# MCU.net
KiCad netlist of a schematic drawn in Altium Designer
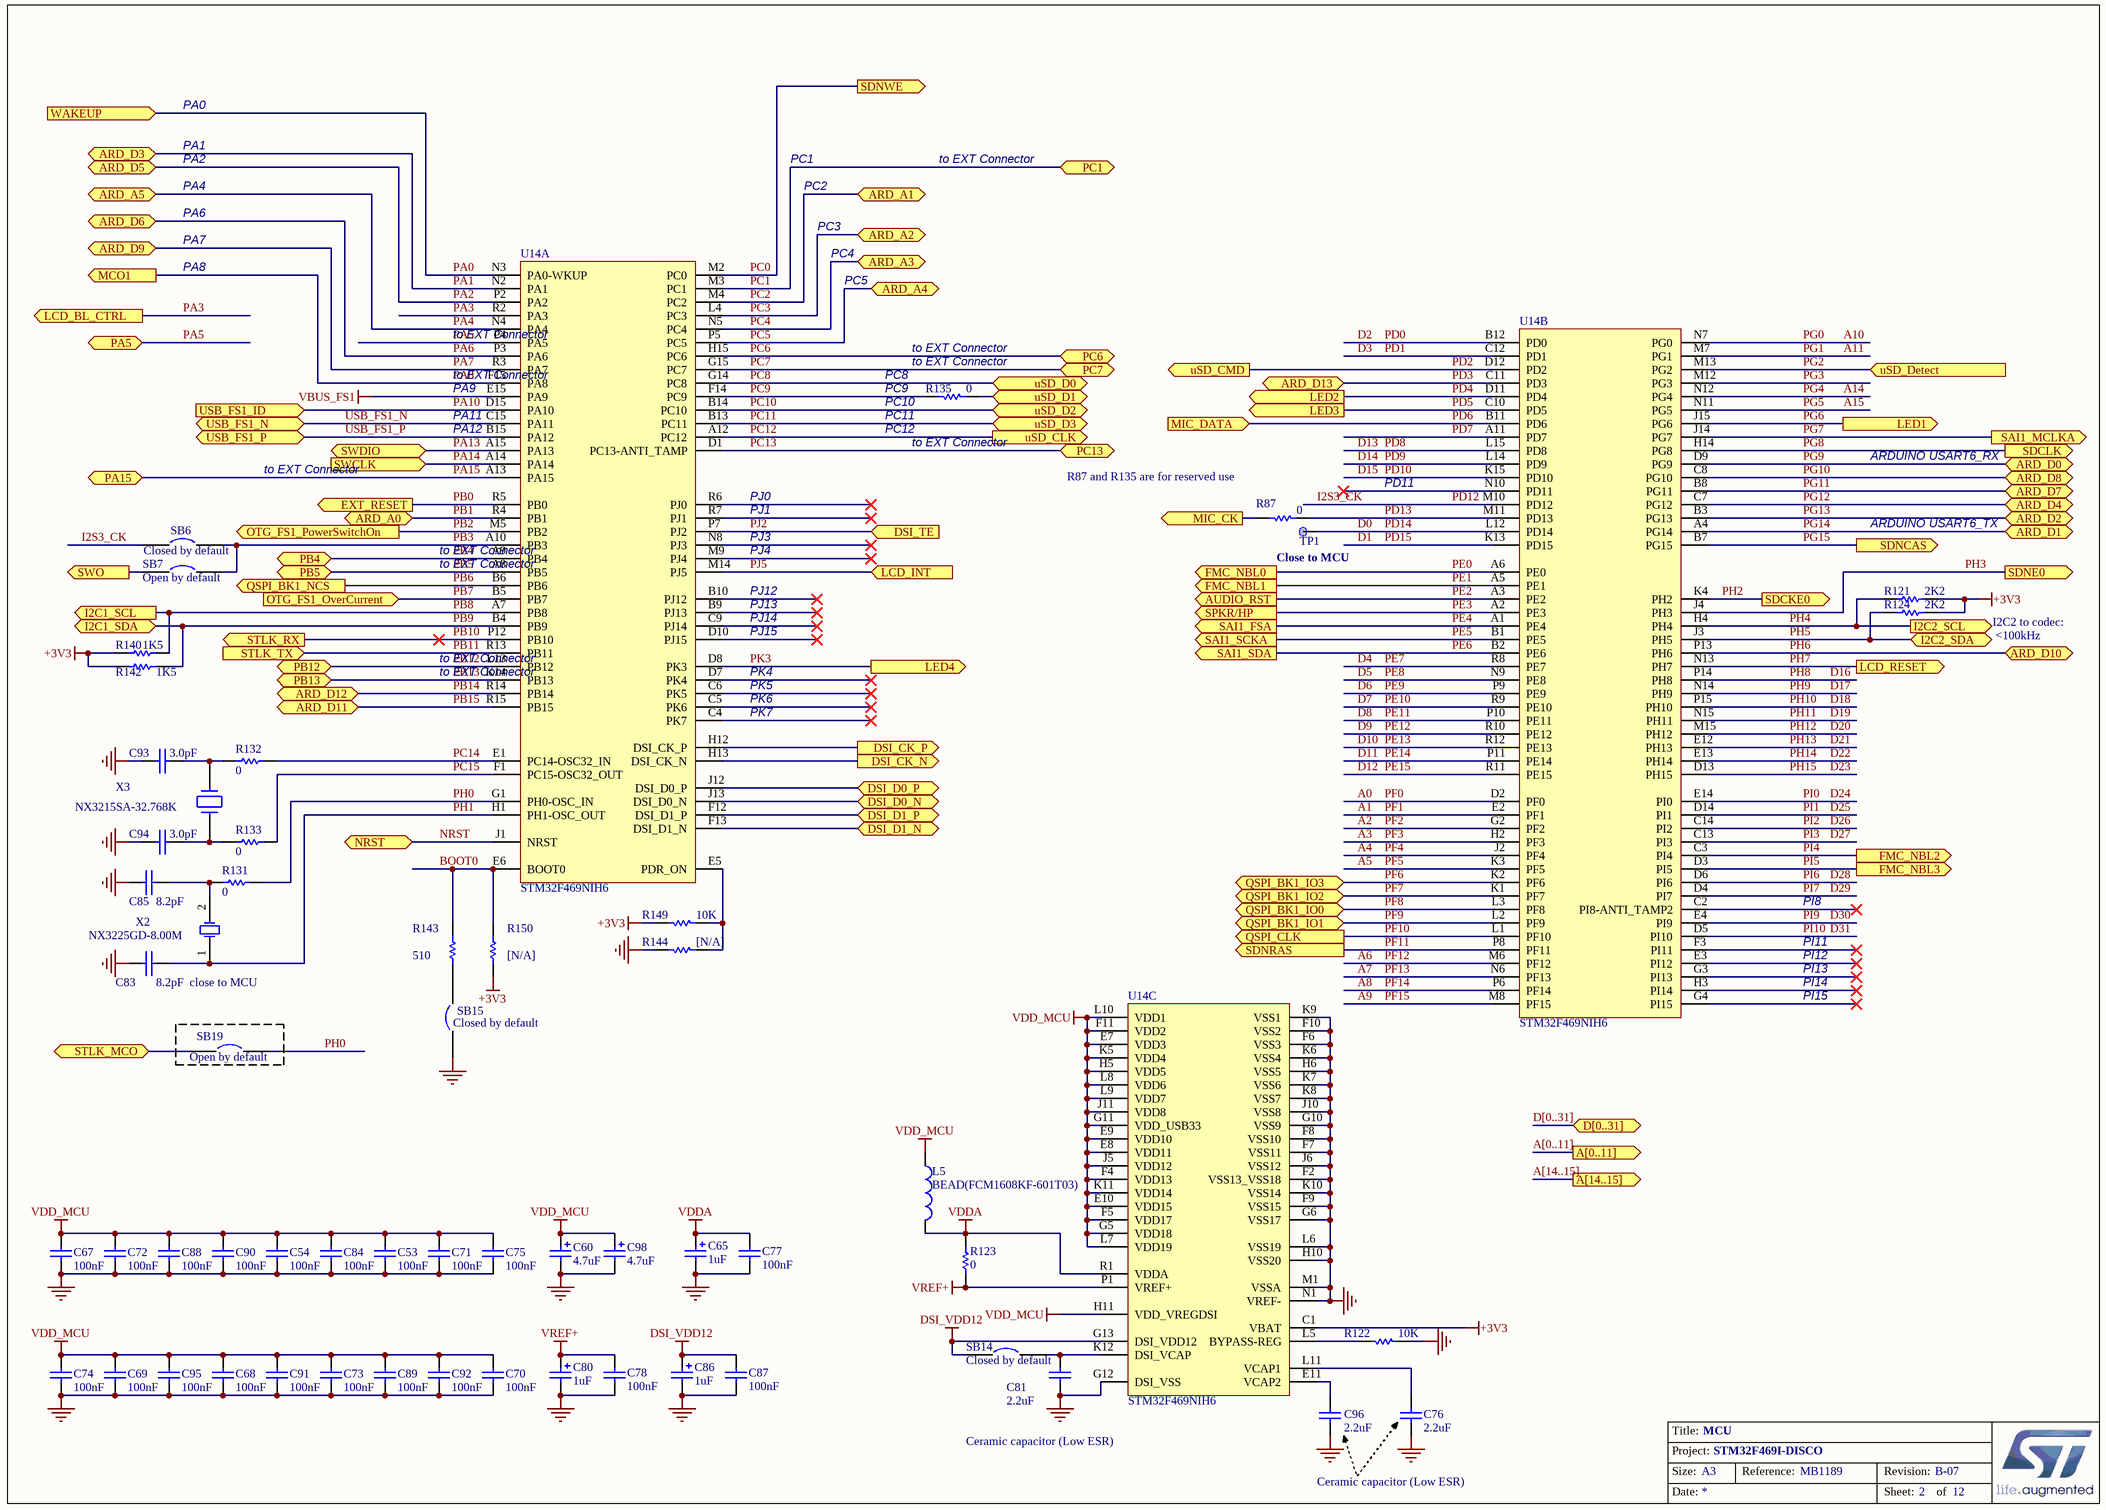
[diagram p0: MCU.SchDoc]

(export (version "E")
  (design (tool "Eeschema 10.0.6"))
  (components
    (comp (ref "C53")
      (value "100nF")
      (footprint "0402C")
      (description "Capacitor")
      (fields (field (name "PUBLISHER") "Altium Limited"))
      (libsource (lib "Miscellaneous Devices") (part "CAP"))
    )
    (comp (ref "C54")
      (value "100nF")
      (footprint "0402C")
      (description "Capacitor")
      (fields (field (name "PUBLISHER") "Altium Limited"))
      (libsource (lib "Miscellaneous Devices") (part "CAP"))
    )
    (comp (ref "C60")
      (value "4.7uF")
      (footprint "TAN-A")
      (description "Polarized Capacitor (Radial)")
      (fields (field (name "PUBLISHER") "Altium Limited"))
      (libsource (lib "Miscellaneous Devices") (part "Cap Pol1"))
    )
    (comp (ref "C65")
      (value "1uF")
      (footprint "TAN-A")
      (description "Polarized Capacitor (Radial)")
      (fields (field (name "PUBLISHER") "Altium Limited"))
      (libsource (lib "Miscellaneous Devices") (part "Cap Pol1"))
    )
    (comp (ref "C67")
      (value "100nF")
      (footprint "0402C")
      (description "Capacitor")
      (fields (field (name "PUBLISHER") "Altium Limited"))
      (libsource (lib "Miscellaneous Devices") (part "CAP"))
    )
    (comp (ref "C68")
      (value "100nF")
      (footprint "0402C")
      (description "Capacitor")
      (fields (field (name "PUBLISHER") "Altium Limited"))
      (libsource (lib "Miscellaneous Devices") (part "CAP"))
    )
    (comp (ref "C69")
      (value "100nF")
      (footprint "0402C")
      (description "Capacitor")
      (fields (field (name "PUBLISHER") "Altium Limited"))
      (libsource (lib "Miscellaneous Devices") (part "CAP"))
    )
    (comp (ref "C70")
      (value "100nF")
      (footprint "0402C")
      (description "Capacitor")
      (fields (field (name "PUBLISHER") "Altium Limited"))
      (libsource (lib "Miscellaneous Devices") (part "CAP"))
    )
    (comp (ref "C71")
      (value "100nF")
      (footprint "0402C")
      (description "Capacitor")
      (fields (field (name "PUBLISHER") "Altium Limited"))
      (libsource (lib "Miscellaneous Devices") (part "CAP"))
    )
    (comp (ref "C72")
      (value "100nF")
      (footprint "0402C")
      (description "Capacitor")
      (fields (field (name "PUBLISHER") "Altium Limited"))
      (libsource (lib "Miscellaneous Devices") (part "CAP"))
    )
    (comp (ref "C73")
      (value "100nF")
      (footprint "0402C")
      (description "Capacitor")
      (fields (field (name "PUBLISHER") "Altium Limited"))
      (libsource (lib "Miscellaneous Devices") (part "CAP"))
    )
    (comp (ref "C74")
      (value "100nF")
      (footprint "0402C")
      (description "Capacitor")
      (fields (field (name "PUBLISHER") "Altium Limited"))
      (libsource (lib "Miscellaneous Devices") (part "CAP"))
    )
    (comp (ref "C75")
      (value "100nF")
      (footprint "0402C")
      (description "Capacitor")
      (fields (field (name "PUBLISHER") "Altium Limited"))
      (libsource (lib "Miscellaneous Devices") (part "CAP"))
    )
    (comp (ref "C76")
      (value "2.2uF")
      (footprint "1206C")
      (description "Capacitor")
      (fields (field (name "PUBLISHER") "Altium Limited"))
      (libsource (lib "Miscellaneous Devices") (part "Cap"))
    )
    (comp (ref "C77")
      (value "100nF")
      (footprint "0402C")
      (description "Capacitor")
      (fields (field (name "PUBLISHER") "Altium Limited"))
      (libsource (lib "Miscellaneous Devices") (part "Cap"))
    )
    (comp (ref "C78")
      (value "100nF")
      (footprint "0402C")
      (description "Capacitor")
      (fields (field (name "PUBLISHER") "Altium Limited"))
      (libsource (lib "Miscellaneous Devices") (part "Cap"))
    )
    (comp (ref "C80")
      (value "1uF")
      (footprint "TAN-A")
      (description "Polarized Capacitor (Radial)")
      (fields (field (name "PUBLISHER") "Altium Limited"))
      (libsource (lib "Miscellaneous Devices") (part "Cap Pol1"))
    )
    (comp (ref "C81")
      (value "2.2uF")
      (footprint "1206C")
      (description "Capacitor")
      (fields (field (name "PUBLISHER") "Altium Limited"))
      (libsource (lib "Miscellaneous Devices") (part "Cap"))
    )
    (comp (ref "C83")
      (value "8.2pF")
      (footprint "0603C")
      (description "Capacitor")
      (libsource (lib "*") (part "CAP"))
    )
    (comp (ref "C84")
      (value "100nF")
      (footprint "0402C")
      (description "Capacitor")
      (fields (field (name "PUBLISHER") "Altium Limited"))
      (libsource (lib "Miscellaneous Devices") (part "CAP"))
    )
    (comp (ref "C85")
      (value "8.2pF")
      (footprint "0603C")
      (description "Capacitor")
      (libsource (lib "*") (part "CAP"))
    )
    (comp (ref "C86")
      (value "1uF")
      (footprint "TAN-A")
      (description "Polarized Capacitor (Radial)")
      (fields (field (name "PUBLISHER") "Altium Limited"))
      (libsource (lib "Miscellaneous Devices") (part "Cap Pol1"))
    )
    (comp (ref "C87")
      (value "100nF")
      (footprint "0402C")
      (description "Capacitor")
      (fields (field (name "PUBLISHER") "Altium Limited"))
      (libsource (lib "Miscellaneous Devices") (part "Cap"))
    )
    (comp (ref "C88")
      (value "100nF")
      (footprint "0402C")
      (description "Capacitor")
      (fields (field (name "PUBLISHER") "Altium Limited"))
      (libsource (lib "Miscellaneous Devices") (part "CAP"))
    )
    (comp (ref "C89")
      (value "100nF")
      (footprint "0402C")
      (description "Capacitor")
      (fields (field (name "PUBLISHER") "Altium Limited"))
      (libsource (lib "Miscellaneous Devices") (part "CAP"))
    )
    (comp (ref "C90")
      (value "100nF")
      (footprint "0402C")
      (description "Capacitor")
      (fields (field (name "PUBLISHER") "Altium Limited"))
      (libsource (lib "Miscellaneous Devices") (part "CAP"))
    )
    (comp (ref "C91")
      (value "100nF")
      (footprint "0402C")
      (description "Capacitor")
      (fields (field (name "PUBLISHER") "Altium Limited"))
      (libsource (lib "Miscellaneous Devices") (part "CAP"))
    )
    (comp (ref "C92")
      (value "100nF")
      (footprint "0402C")
      (description "Capacitor")
      (fields (field (name "PUBLISHER") "Altium Limited"))
      (libsource (lib "Miscellaneous Devices") (part "CAP"))
    )
    (comp (ref "C93")
      (value "3.0pF")
      (footprint "0603C")
      (description "Capacitor")
      (libsource (lib "") (part "CAP_1"))
    )
    (comp (ref "C94")
      (value "3.0pF")
      (footprint "0603C")
      (description "Capacitor")
      (libsource (lib "") (part "CAP_1"))
    )
    (comp (ref "C95")
      (value "100nF")
      (footprint "0402C")
      (description "Capacitor")
      (fields (field (name "PUBLISHER") "Altium Limited"))
      (libsource (lib "Miscellaneous Devices") (part "CAP"))
    )
    (comp (ref "C96")
      (value "2.2uF")
      (footprint "1206C")
      (description "Capacitor")
      (fields (field (name "PUBLISHER") "Altium Limited"))
      (libsource (lib "Miscellaneous Devices") (part "Cap"))
    )
    (comp (ref "C98")
      (value "4.7uF")
      (footprint "TAN-A")
      (description "Polarized Capacitor (Radial)")
      (fields (field (name "PUBLISHER") "Altium Limited"))
      (libsource (lib "Miscellaneous Devices") (part "Cap Pol1"))
    )
    (comp (ref "L5")
      (value "BEAD(FCM1608KF-601T03)")
      (footprint "0603L")
      (description "Inductor")
      (fields (field (name "PUBLISHER") "Altium Limited"))
      (libsource (lib "Miscellaneous Devices") (part "Inductor"))
    )
    (comp (ref "R87")
      (value "0")
      (footprint "0603R")
      (description "Resistor")
      (fields (field (name "PUBLISHER") "Altium Limited"))
      (libsource (lib "Miscellaneous Devices") (part "Res1"))
    )
    (comp (ref "R121")
      (value "2K2")
      (footprint "0603R")
      (description "Resistor")
      (fields (field (name "PUBLISHER") "Altium Limited"))
      (libsource (lib "") (part "Res1_1"))
    )
    (comp (ref "R122")
      (value "10K")
      (footprint "0402R")
      (description "Resistor")
      (fields (field (name "PUBLISHER") "Altium Limited"))
      (libsource (lib "") (part "Res1_1"))
    )
    (comp (ref "R123")
      (value "0")
      (footprint "0603R")
      (description "Resistor")
      (fields (field (name "PUBLISHER") "Altium Limited"))
      (libsource (lib "Miscellaneous Devices") (part "Res1"))
    )
    (comp (ref "R124")
      (value "2K2")
      (footprint "0603R")
      (description "Resistor")
      (fields (field (name "PUBLISHER") "Altium Limited"))
      (libsource (lib "") (part "Res1_1"))
    )
    (comp (ref "R131")
      (value "0")
      (footprint "0603R")
      (description "Resistor")
      (fields (field (name "PUBLISHER") "Altium Limited"))
      (libsource (lib "Miscellaneous Devices") (part "Res1"))
    )
    (comp (ref "R132")
      (value "0")
      (footprint "0603R")
      (description "Resistor")
      (fields (field (name "PUBLISHER") "Altium Limited"))
      (libsource (lib "") (part "Res1_1"))
    )
    (comp (ref "R133")
      (value "0")
      (footprint "0603R")
      (description "Resistor")
      (fields (field (name "PUBLISHER") "Altium Limited"))
      (libsource (lib "") (part "Res1_1"))
    )
    (comp (ref "R135")
      (value "0")
      (footprint "0603R")
      (description "Resistor")
      (fields (field (name "PUBLISHER") "Altium Limited"))
      (libsource (lib "Miscellaneous Devices") (part "Res1"))
    )
    (comp (ref "R140")
      (value "1K5")
      (footprint "0603R")
      (description "Resistor")
      (fields (field (name "PUBLISHER") "Altium Limited"))
      (libsource (lib "") (part "Res1_1"))
    )
    (comp (ref "R142")
      (value "1K5")
      (footprint "0603R")
      (description "Resistor")
      (fields (field (name "PUBLISHER") "Altium Limited"))
      (libsource (lib "") (part "Res1_1"))
    )
    (comp (ref "R143")
      (value "510")
      (footprint "0603R")
      (description "Resistor")
      (fields (field (name "PUBLISHER") "Altium Limited"))
      (libsource (lib "Miscellaneous Devices") (part "res1"))
    )
    (comp (ref "R144")
      (value "[N/A]")
      (footprint "0603R")
      (description "Resistor")
      (fields (field (name "PUBLISHER") "Altium Limited"))
      (libsource (lib "Miscellaneous Devices") (part "Res1"))
    )
    (comp (ref "R149")
      (value "10K")
      (footprint "0402R")
      (description "Resistor")
      (fields (field (name "PUBLISHER") "Altium Limited"))
      (libsource (lib "Miscellaneous Devices") (part "Res1"))
    )
    (comp (ref "R150")
      (value "[N/A]")
      (footprint "0603R")
      (description "Resistor")
      (fields (field (name "PUBLISHER") "Altium Limited"))
      (libsource (lib "Miscellaneous Devices") (part "res1"))
    )
    (comp (ref "SB6")
      (value "Closed by default")
      (footprint "SB_0603")
      (description "Circuit Breaker")
      (fields (field (name "PUBLISHER") "Altium Limited"))
      (libsource (lib "Miscellaneous Devices") (part "Circuit Breaker"))
    )
    (comp (ref "SB7")
      (value "Open by default")
      (footprint "SB_0603")
      (description "Circuit Breaker")
      (fields (field (name "PUBLISHER") "Altium Limited"))
      (libsource (lib "Miscellaneous Devices") (part "Circuit Breaker"))
    )
    (comp (ref "SB14")
      (value "Closed by default")
      (footprint "SB_0603")
      (description "Circuit Breaker")
      (fields (field (name "PUBLISHER") "Altium Limited"))
      (libsource (lib "Miscellaneous Devices") (part "Circuit Breaker"))
    )
    (comp (ref "SB15")
      (value "Closed by default")
      (footprint "SB_0603")
      (description "Circuit Breaker")
      (fields (field (name "PUBLISHER") "Altium Limited"))
      (libsource (lib "Miscellaneous Devices") (part "Circuit Breaker"))
    )
    (comp (ref "SB19")
      (value "Open by default")
      (footprint "SB_0603")
      (description "Circuit Breaker")
      (fields (field (name "PUBLISHER") "Altium Limited"))
      (libsource (lib "Miscellaneous Devices") (part "Circuit Breaker"))
    )
    (comp (ref "TP1") (value "TP") (footprint "TP_C40") (libsource (lib "Almos") (part "TP")))
    (comp (ref "U14")
      (value "STM32F469NIH6")
      (footprint "BGA216_0R8_13X13")
      (libsource (lib "MB1165") (part "Manta_Dragon_TFBGA216"))
    )
    (comp (ref "X2")
      (value "NX3225GD-8.00M")
      (footprint "XTAL_2SM_3R2X2R5_H1")
      (description "Crystal 8Mhz, 8pF, -+50PPM, SMD")
      (libsource (lib "MCD_TOOLS") (part "XTAL_8M_NX3225GD"))
    )
    (comp (ref "X3")
      (value "NX3215SA-32.768K")
      (footprint "XTAL_2SM_3R2X1R5")
      (description "Crystal 32.768kHz, 6pF, -+20PPM, NDK only for ST, Type NX3215SA,  NDK Spec EXS00A-MU00525")
      (libsource (lib "MCD_TOOLS") (part "XTAL_32K_NX3215SA"))
    )
  )
  (nets
    (net (code "1") (name "+3V3") (class "Default")
      (node (ref "R121") (pin "1") (pinfunction "1_1") (pintype "passive"))
      (node (ref "R124") (pin "1") (pinfunction "1_1") (pintype "passive"))
      (node (ref "R140") (pin "1") (pinfunction "1_1") (pintype "passive"))
      (node (ref "R142") (pin "1") (pinfunction "1_1") (pintype "passive"))
      (node (ref "R149") (pin "2") (pinfunction "2_2") (pintype "passive"))
      (node (ref "R150") (pin "2") (pinfunction "2_2") (pintype "passive"))
      (node (ref "U14") (pin "C1") (pinfunction "VBAT_C1") (pintype "passive"))
    )
    (net (code "2") (name "/A0") (class "Default")
      (node (ref "U14") (pin "D2") (pinfunction "PF0_D2") (pintype "passive"))
    )
    (net (code "3") (name "/A1") (class "Default")
      (node (ref "U14") (pin "E2") (pinfunction "PF1_E2") (pintype "passive"))
    )
    (net (code "4") (name "/A2") (class "Default")
      (node (ref "U14") (pin "G2") (pinfunction "PF2_G2") (pintype "passive"))
    )
    (net (code "5") (name "/A3") (class "Default")
      (node (ref "U14") (pin "H2") (pinfunction "PF3_H2") (pintype "passive"))
    )
    (net (code "6") (name "/A4") (class "Default")
      (node (ref "U14") (pin "J2") (pinfunction "PF4_J2") (pintype "passive"))
    )
    (net (code "7") (name "/A5") (class "Default")
      (node (ref "U14") (pin "K3") (pinfunction "PF5_K3") (pintype "passive"))
    )
    (net (code "8") (name "/A6") (class "Default")
      (node (ref "U14") (pin "M6") (pinfunction "PF12_M6") (pintype "passive"))
    )
    (net (code "9") (name "/A7") (class "Default")
      (node (ref "U14") (pin "N6") (pinfunction "PF13_N6") (pintype "passive"))
    )
    (net (code "10") (name "/A8") (class "Default")
      (node (ref "U14") (pin "P6") (pinfunction "PF14_P6") (pintype "passive"))
    )
    (net (code "11") (name "/A9") (class "Default")
      (node (ref "U14") (pin "M8") (pinfunction "PF15_M8") (pintype "passive"))
    )
    (net (code "12") (name "/A10") (class "Default")
      (node (ref "U14") (pin "N7") (pinfunction "PG0_N7") (pintype "passive"))
    )
    (net (code "13") (name "/A11") (class "Default")
      (node (ref "U14") (pin "M7") (pinfunction "PG1_M7") (pintype "passive"))
    )
    (net (code "14") (name "/A14") (class "Default")
      (node (ref "U14") (pin "N12") (pinfunction "PG4_N12") (pintype "passive"))
    )
    (net (code "15") (name "/A15") (class "Default")
      (node (ref "U14") (pin "N11") (pinfunction "PG5_N11") (pintype "passive"))
    )
    (net (code "18") (name "/BOOT0") (class "Default")
      (node (ref "R143") (pin "1") (pinfunction "1_1") (pintype "passive"))
      (node (ref "R150") (pin "1") (pinfunction "1_1") (pintype "passive"))
      (node (ref "U14") (pin "E6") (pinfunction "BOOT0_E6") (pintype "passive"))
    )
    (net (code "19") (name "/D0") (class "Default")
      (node (ref "TP1") (pin "1") (pinfunction "1_1") (pintype "passive"))
      (node (ref "U14") (pin "L12") (pinfunction "PD14_L12") (pintype "passive"))
    )
    (net (code "20") (name "/D1") (class "Default")
      (node (ref "U14") (pin "K13") (pinfunction "PD15_K13") (pintype "passive"))
    )
    (net (code "21") (name "/D2") (class "Default")
      (node (ref "U14") (pin "B12") (pinfunction "PD0_B12") (pintype "passive"))
    )
    (net (code "22") (name "/D3") (class "Default")
      (node (ref "U14") (pin "C12") (pinfunction "PD1_C12") (pintype "passive"))
    )
    (net (code "23") (name "/D4") (class "Default")
      (node (ref "U14") (pin "R8") (pinfunction "PE7_R8") (pintype "passive"))
    )
    (net (code "24") (name "/D5") (class "Default")
      (node (ref "U14") (pin "N9") (pinfunction "PE8_N9") (pintype "passive"))
    )
    (net (code "25") (name "/D6") (class "Default")
      (node (ref "U14") (pin "P9") (pinfunction "PE9_P9") (pintype "passive"))
    )
    (net (code "26") (name "/D7") (class "Default")
      (node (ref "U14") (pin "R9") (pinfunction "PE10_R9") (pintype "passive"))
    )
    (net (code "27") (name "/D8") (class "Default")
      (node (ref "U14") (pin "P10") (pinfunction "PE11_P10") (pintype "passive"))
    )
    (net (code "28") (name "/D9") (class "Default")
      (node (ref "U14") (pin "R10") (pinfunction "PE12_R10") (pintype "passive"))
    )
    (net (code "29") (name "/D10") (class "Default")
      (node (ref "U14") (pin "R12") (pinfunction "PE13_R12") (pintype "passive"))
    )
    (net (code "30") (name "/D11") (class "Default")
      (node (ref "U14") (pin "P11") (pinfunction "PE14_P11") (pintype "passive"))
    )
    (net (code "31") (name "/D12") (class "Default")
      (node (ref "U14") (pin "R11") (pinfunction "PE15_R11") (pintype "passive"))
    )
    (net (code "32") (name "/D13") (class "Default")
      (node (ref "U14") (pin "L15") (pinfunction "PD8_L15") (pintype "passive"))
    )
    (net (code "33") (name "/D14") (class "Default")
      (node (ref "U14") (pin "L14") (pinfunction "PD9_L14") (pintype "passive"))
    )
    (net (code "34") (name "/D15") (class "Default")
      (node (ref "U14") (pin "K15") (pinfunction "PD10_K15") (pintype "passive"))
    )
    (net (code "35") (name "/D16") (class "Default")
      (node (ref "U14") (pin "P14") (pinfunction "PH8_P14") (pintype "passive"))
    )
    (net (code "36") (name "/D17") (class "Default")
      (node (ref "U14") (pin "N14") (pinfunction "PH9_N14") (pintype "passive"))
    )
    (net (code "37") (name "/D18") (class "Default")
      (node (ref "U14") (pin "P15") (pinfunction "PH10_P15") (pintype "passive"))
    )
    (net (code "38") (name "/D19") (class "Default")
      (node (ref "U14") (pin "N15") (pinfunction "PH11_N15") (pintype "passive"))
    )
    (net (code "39") (name "/D20") (class "Default")
      (node (ref "U14") (pin "M15") (pinfunction "PH12_M15") (pintype "passive"))
    )
    (net (code "40") (name "/D21") (class "Default")
      (node (ref "U14") (pin "E12") (pinfunction "PH13_E12") (pintype "passive"))
    )
    (net (code "41") (name "/D22") (class "Default")
      (node (ref "U14") (pin "E13") (pinfunction "PH14_E13") (pintype "passive"))
    )
    (net (code "42") (name "/D23") (class "Default")
      (node (ref "U14") (pin "D13") (pinfunction "PH15_D13") (pintype "passive"))
    )
    (net (code "43") (name "/D24") (class "Default")
      (node (ref "U14") (pin "E14") (pinfunction "PI0_E14") (pintype "passive"))
    )
    (net (code "44") (name "/D25") (class "Default")
      (node (ref "U14") (pin "D14") (pinfunction "PI1_D14") (pintype "passive"))
    )
    (net (code "45") (name "/D26") (class "Default")
      (node (ref "U14") (pin "C14") (pinfunction "PI2_C14") (pintype "passive"))
    )
    (net (code "46") (name "/D27") (class "Default")
      (node (ref "U14") (pin "C13") (pinfunction "PI3_C13") (pintype "passive"))
    )
    (net (code "47") (name "/D28") (class "Default")
      (node (ref "U14") (pin "D6") (pinfunction "PI6_D6") (pintype "passive"))
    )
    (net (code "48") (name "/D29") (class "Default")
      (node (ref "U14") (pin "D4") (pinfunction "PI7_D4") (pintype "passive"))
    )
    (net (code "49") (name "/D30") (class "Default")
      (node (ref "U14") (pin "E4") (pinfunction "PI9_E4") (pintype "passive"))
    )
    (net (code "50") (name "/D31") (class "Default")
      (node (ref "U14") (pin "D5") (pinfunction "PI10_D5") (pintype "passive"))
    )
    (net (code "51") (name "/DSI_CK_N") (class "Default")
      (node (ref "U14") (pin "H13") (pinfunction "DSI_CK_N_H13") (pintype "passive"))
    )
    (net (code "52") (name "/DSI_CK_P") (class "Default")
      (node (ref "U14") (pin "H12") (pinfunction "DSI_CK_P_H12") (pintype "passive"))
    )
    (net (code "53") (name "/DSI_D0_N") (class "Default")
      (node (ref "U14") (pin "J13") (pinfunction "DSI_D0_N_J13") (pintype "passive"))
    )
    (net (code "54") (name "/DSI_D0_P") (class "Default")
      (node (ref "U14") (pin "J12") (pinfunction "DSI_D0_P_J12") (pintype "passive"))
    )
    (net (code "55") (name "/DSI_D1_N") (class "Default")
      (node (ref "U14") (pin "F13") (pinfunction "DSI_D1_N_F13") (pintype "passive"))
    )
    (net (code "56") (name "/DSI_D1_P") (class "Default")
      (node (ref "U14") (pin "F12") (pinfunction "DSI_D1_P_F12") (pintype "passive"))
    )
    (net (code "58") (name "/I2S3_CK") (class "Default")
      (node (ref "SB6") (pin "1") (pinfunction "1_1") (pintype "passive"))
      (node (ref "U14") (pin "M10") (pinfunction "PD12_M10") (pintype "passive"))
    )
    (net (code "59") (name "/MIC_CK") (class "Default")
      (node (ref "R87") (pin "1") (pinfunction "1_1") (pintype "passive"))
    )
    (net (code "60") (name "/NRST") (class "Default")
      (node (ref "U14") (pin "J1") (pinfunction "NRST_J1") (pintype "passive"))
    )
    (net (code "61") (name "/PA0") (class "Default")
      (node (ref "U14") (pin "N3") (pinfunction "PA0-WKUP_N3") (pintype "passive"))
    )
    (net (code "62") (name "/PA1") (class "Default")
      (node (ref "U14") (pin "N2") (pinfunction "PA1_N2") (pintype "passive"))
    )
    (net (code "63") (name "/PA2") (class "Default")
      (node (ref "U14") (pin "P2") (pinfunction "PA2_P2") (pintype "passive"))
    )
    (net (code "64") (name "/PA3") (class "Default")
      (node (ref "U14") (pin "R2") (pinfunction "PA3_R2") (pintype "passive"))
    )
    (net (code "65") (name "/PA4") (class "Default")
      (node (ref "U14") (pin "N4") (pinfunction "PA4_N4") (pintype "passive"))
    )
    (net (code "66") (name "/PA5") (class "Default")
      (node (ref "U14") (pin "P4") (pinfunction "PA5_P4") (pintype "passive"))
    )
    (net (code "67") (name "/PA6") (class "Default")
      (node (ref "U14") (pin "P3") (pinfunction "PA6_P3") (pintype "passive"))
    )
    (net (code "68") (name "/PA7") (class "Default")
      (node (ref "U14") (pin "R3") (pinfunction "PA7_R3") (pintype "passive"))
    )
    (net (code "69") (name "/PA8") (class "Default")
      (node (ref "U14") (pin "F15") (pinfunction "PA8_F15") (pintype "passive"))
    )
    (net (code "70") (name "/PA10") (class "Default")
      (node (ref "U14") (pin "D15") (pinfunction "PA10_D15") (pintype "passive"))
    )
    (net (code "71") (name "/PA13") (class "Default")
      (node (ref "U14") (pin "A15") (pinfunction "PA13_A15") (pintype "passive"))
    )
    (net (code "72") (name "/PA14") (class "Default")
      (node (ref "U14") (pin "A14") (pinfunction "PA14_A14") (pintype "passive"))
    )
    (net (code "73") (name "/PA15") (class "Default")
      (node (ref "U14") (pin "A13") (pinfunction "PA15_A13") (pintype "passive"))
    )
    (net (code "74") (name "/PB0") (class "Default")
      (node (ref "U14") (pin "R5") (pinfunction "PB0_R5") (pintype "passive"))
    )
    (net (code "75") (name "/PB1") (class "Default")
      (node (ref "U14") (pin "R4") (pinfunction "PB1_R4") (pintype "passive"))
    )
    (net (code "76") (name "/PB2") (class "Default")
      (node (ref "U14") (pin "M5") (pinfunction "PB2_M5") (pintype "passive"))
    )
    (net (code "77") (name "/PB3") (class "Default")
      (node (ref "SB6") (pin "2") (pinfunction "2_2") (pintype "passive"))
      (node (ref "SB7") (pin "2") (pinfunction "2_2") (pintype "passive"))
      (node (ref "U14") (pin "A10") (pinfunction "PB3_A10") (pintype "passive"))
    )
    (net (code "78") (name "/PB4") (class "Default")
      (node (ref "U14") (pin "A9") (pinfunction "PB4_A9") (pintype "passive"))
    )
    (net (code "79") (name "/PB5") (class "Default")
      (node (ref "U14") (pin "A8") (pinfunction "PB5_A8") (pintype "passive"))
    )
    (net (code "80") (name "/PB6") (class "Default")
      (node (ref "U14") (pin "B6") (pinfunction "PB6_B6") (pintype "passive"))
    )
    (net (code "81") (name "/PB7") (class "Default")
      (node (ref "U14") (pin "B5") (pinfunction "PB7_B5") (pintype "passive"))
    )
    (net (code "82") (name "/PB8") (class "Default")
      (node (ref "R140") (pin "2") (pinfunction "2_2") (pintype "passive"))
      (node (ref "U14") (pin "A7") (pinfunction "PB8_A7") (pintype "passive"))
    )
    (net (code "83") (name "/PB9") (class "Default")
      (node (ref "R142") (pin "2") (pinfunction "2_2") (pintype "passive"))
      (node (ref "U14") (pin "B4") (pinfunction "PB9_B4") (pintype "passive"))
    )
    (net (code "84") (name "/PB10") (class "Default")
      (node (ref "U14") (pin "P12") (pinfunction "PB10_P12") (pintype "passive"))
    )
    (net (code "85") (name "/PB11") (class "Default")
      (node (ref "U14") (pin "R13") (pinfunction "PB11_R13") (pintype "passive"))
    )
    (net (code "86") (name "/PB12") (class "Default")
      (node (ref "U14") (pin "L13") (pinfunction "PB12_L13") (pintype "passive"))
    )
    (net (code "87") (name "/PB13") (class "Default")
      (node (ref "U14") (pin "K14") (pinfunction "PB13_K14") (pintype "passive"))
    )
    (net (code "88") (name "/PB14") (class "Default")
      (node (ref "U14") (pin "R14") (pinfunction "PB14_R14") (pintype "passive"))
    )
    (net (code "89") (name "/PB15") (class "Default")
      (node (ref "U14") (pin "R15") (pinfunction "PB15_R15") (pintype "passive"))
    )
    (net (code "90") (name "/PC0") (class "Default")
      (node (ref "U14") (pin "M2") (pinfunction "PC0_M2") (pintype "passive"))
    )
    (net (code "91") (name "/PC1") (class "Default")
      (node (ref "U14") (pin "M3") (pinfunction "PC1_M3") (pintype "passive"))
    )
    (net (code "92") (name "/PC2") (class "Default")
      (node (ref "U14") (pin "M4") (pinfunction "PC2_M4") (pintype "passive"))
    )
    (net (code "93") (name "/PC3") (class "Default")
      (node (ref "U14") (pin "L4") (pinfunction "PC3_L4") (pintype "passive"))
    )
    (net (code "94") (name "/PC4") (class "Default")
      (node (ref "U14") (pin "N5") (pinfunction "PC4_N5") (pintype "passive"))
    )
    (net (code "95") (name "/PC5") (class "Default")
      (node (ref "U14") (pin "P5") (pinfunction "PC5_P5") (pintype "passive"))
    )
    (net (code "96") (name "/PC6") (class "Default")
      (node (ref "U14") (pin "H15") (pinfunction "PC6_H15") (pintype "passive"))
    )
    (net (code "97") (name "/PC7") (class "Default")
      (node (ref "U14") (pin "G15") (pinfunction "PC7_G15") (pintype "passive"))
    )
    (net (code "98") (name "/PC8") (class "Default")
      (node (ref "U14") (pin "G14") (pinfunction "PC8_G14") (pintype "passive"))
    )
    (net (code "99") (name "/PC9") (class "Default")
      (node (ref "R135") (pin "1") (pinfunction "1_1") (pintype "passive"))
      (node (ref "U14") (pin "F14") (pinfunction "PC9_F14") (pintype "passive"))
    )
    (net (code "100") (name "/PC10") (class "Default")
      (node (ref "U14") (pin "B14") (pinfunction "PC10_B14") (pintype "passive"))
    )
    (net (code "101") (name "/PC11") (class "Default")
      (node (ref "U14") (pin "B13") (pinfunction "PC11_B13") (pintype "passive"))
    )
    (net (code "102") (name "/PC12") (class "Default")
      (node (ref "U14") (pin "A12") (pinfunction "PC12_A12") (pintype "passive"))
    )
    (net (code "103") (name "/PC13") (class "Default")
      (node (ref "U14") (pin "D1") (pinfunction "PC13-ANTI_TAMP_D1") (pintype "passive"))
    )
    (net (code "104") (name "/PC14") (class "Default")
      (node (ref "R132") (pin "2") (pinfunction "2_2") (pintype "passive"))
      (node (ref "U14") (pin "E1") (pinfunction "PC14-OSC32_IN_E1") (pintype "passive"))
    )
    (net (code "105") (name "/PC15") (class "Default")
      (node (ref "R133") (pin "2") (pinfunction "2_2") (pintype "passive"))
      (node (ref "U14") (pin "F1") (pinfunction "PC15-OSC32_OUT_F1") (pintype "passive"))
    )
    (net (code "106") (name "/PD2") (class "Default")
      (node (ref "U14") (pin "D12") (pinfunction "PD2_D12") (pintype "passive"))
    )
    (net (code "107") (name "/PD3") (class "Default")
      (node (ref "U14") (pin "C11") (pinfunction "PD3_C11") (pintype "passive"))
    )
    (net (code "108") (name "/PD4") (class "Default")
      (node (ref "U14") (pin "D11") (pinfunction "PD4_D11") (pintype "passive"))
    )
    (net (code "109") (name "/PD5") (class "Default")
      (node (ref "U14") (pin "C10") (pinfunction "PD5_C10") (pintype "passive"))
    )
    (net (code "110") (name "/PD6") (class "Default")
      (node (ref "U14") (pin "B11") (pinfunction "PD6_B11") (pintype "passive"))
    )
    (net (code "111") (name "/PD7") (class "Default")
      (node (ref "U14") (pin "A11") (pinfunction "PD7_A11") (pintype "passive"))
    )
    (net (code "112") (name "/PD13") (class "Default")
      (node (ref "R87") (pin "2") (pinfunction "2_2") (pintype "passive"))
      (node (ref "U14") (pin "M11") (pinfunction "PD13_M11") (pintype "passive"))
    )
    (net (code "113") (name "/PE0") (class "Default")
      (node (ref "U14") (pin "A6") (pinfunction "PE0_A6") (pintype "passive"))
    )
    (net (code "114") (name "/PE1") (class "Default")
      (node (ref "U14") (pin "A5") (pinfunction "PE1_A5") (pintype "passive"))
    )
    (net (code "115") (name "/PE2") (class "Default")
      (node (ref "U14") (pin "A3") (pinfunction "PE2_A3") (pintype "passive"))
    )
    (net (code "116") (name "/PE3") (class "Default")
      (node (ref "U14") (pin "A2") (pinfunction "PE3_A2") (pintype "passive"))
    )
    (net (code "117") (name "/PE4") (class "Default")
      (node (ref "U14") (pin "A1") (pinfunction "PE4_A1") (pintype "passive"))
    )
    (net (code "118") (name "/PE5") (class "Default")
      (node (ref "U14") (pin "B1") (pinfunction "PE5_B1") (pintype "passive"))
    )
    (net (code "119") (name "/PE6") (class "Default")
      (node (ref "U14") (pin "B2") (pinfunction "PE6_B2") (pintype "passive"))
    )
    (net (code "120") (name "/PF6") (class "Default")
      (node (ref "U14") (pin "K2") (pinfunction "PF6_K2") (pintype "passive"))
    )
    (net (code "121") (name "/PF7") (class "Default")
      (node (ref "U14") (pin "K1") (pinfunction "PF7_K1") (pintype "passive"))
    )
    (net (code "122") (name "/PF8") (class "Default")
      (node (ref "U14") (pin "L3") (pinfunction "PF8_L3") (pintype "passive"))
    )
    (net (code "123") (name "/PF9") (class "Default")
      (node (ref "U14") (pin "L2") (pinfunction "PF9_L2") (pintype "passive"))
    )
    (net (code "124") (name "/PF10") (class "Default")
      (node (ref "U14") (pin "L1") (pinfunction "PF10_L1") (pintype "passive"))
    )
    (net (code "125") (name "/PF11") (class "Default")
      (node (ref "U14") (pin "P8") (pinfunction "PF11_P8") (pintype "passive"))
    )
    (net (code "126") (name "/PG2") (class "Default")
      (node (ref "U14") (pin "M13") (pinfunction "PG2_M13") (pintype "passive"))
    )
    (net (code "127") (name "/PG3") (class "Default")
      (node (ref "U14") (pin "M12") (pinfunction "PG3_M12") (pintype "passive"))
    )
    (net (code "128") (name "/PG6") (class "Default")
      (node (ref "U14") (pin "J15") (pinfunction "PG6_J15") (pintype "passive"))
    )
    (net (code "129") (name "/PG7") (class "Default")
      (node (ref "U14") (pin "J14") (pinfunction "PG7_J14") (pintype "passive"))
    )
    (net (code "130") (name "/PG8") (class "Default")
      (node (ref "U14") (pin "H14") (pinfunction "PG8_H14") (pintype "passive"))
    )
    (net (code "131") (name "/PG9") (class "Default")
      (node (ref "U14") (pin "D9") (pinfunction "PG9_D9") (pintype "passive"))
    )
    (net (code "132") (name "/PG10") (class "Default")
      (node (ref "U14") (pin "C8") (pinfunction "PG10_C8") (pintype "passive"))
    )
    (net (code "133") (name "/PG11") (class "Default")
      (node (ref "U14") (pin "B8") (pinfunction "PG11_B8") (pintype "passive"))
    )
    (net (code "134") (name "/PG12") (class "Default")
      (node (ref "U14") (pin "C7") (pinfunction "PG12_C7") (pintype "passive"))
    )
    (net (code "135") (name "/PG13") (class "Default")
      (node (ref "U14") (pin "B3") (pinfunction "PG13_B3") (pintype "passive"))
    )
    (net (code "136") (name "/PG14") (class "Default")
      (node (ref "U14") (pin "A4") (pinfunction "PG14_A4") (pintype "passive"))
    )
    (net (code "137") (name "/PG15") (class "Default")
      (node (ref "U14") (pin "B7") (pinfunction "PG15_B7") (pintype "passive"))
    )
    (net (code "138") (name "/PH0") (class "Default")
      (node (ref "R131") (pin "1") (pinfunction "1_1") (pintype "passive"))
      (node (ref "SB19") (pin "2") (pinfunction "2_2") (pintype "passive"))
      (node (ref "U14") (pin "G1") (pinfunction "PH0-OSC_IN_G1") (pintype "passive"))
    )
    (net (code "139") (name "/PH1") (class "Default")
      (node (ref "C83") (pin "1") (pinfunction "1_1") (pintype "passive"))
      (node (ref "U14") (pin "H1") (pinfunction "PH1-OSC_OUT_H1") (pintype "passive"))
      (node (ref "X2") (pin "1") (pinfunction "OSC1_1") (pintype "passive"))
    )
    (net (code "140") (name "/PH2") (class "Default")
      (node (ref "U14") (pin "K4") (pinfunction "PH2_K4") (pintype "passive"))
    )
    (net (code "141") (name "/PH3") (class "Default")
      (node (ref "U14") (pin "J4") (pinfunction "PH3_J4") (pintype "passive"))
    )
    (net (code "142") (name "/PH4") (class "Default")
      (node (ref "R121") (pin "2") (pinfunction "2_2") (pintype "passive"))
      (node (ref "U14") (pin "H4") (pinfunction "PH4_H4") (pintype "passive"))
    )
    (net (code "143") (name "/PH5") (class "Default")
      (node (ref "R124") (pin "2") (pinfunction "2_2") (pintype "passive"))
      (node (ref "U14") (pin "J3") (pinfunction "PH5_J3") (pintype "passive"))
    )
    (net (code "144") (name "/PH6") (class "Default")
      (node (ref "U14") (pin "P13") (pinfunction "PH6_P13") (pintype "passive"))
    )
    (net (code "145") (name "/PH7") (class "Default")
      (node (ref "U14") (pin "N13") (pinfunction "PH7_N13") (pintype "passive"))
    )
    (net (code "146") (name "/PI4") (class "Default")
      (node (ref "U14") (pin "C3") (pinfunction "PI4_C3") (pintype "passive"))
    )
    (net (code "147") (name "/PI5") (class "Default")
      (node (ref "U14") (pin "D3") (pinfunction "PI5_D3") (pintype "passive"))
    )
    (net (code "148") (name "/PJ2") (class "Default")
      (node (ref "U14") (pin "P7") (pinfunction "PJ2_P7") (pintype "passive"))
    )
    (net (code "149") (name "/PJ5") (class "Default")
      (node (ref "U14") (pin "M14") (pinfunction "PJ5_M14") (pintype "passive"))
    )
    (net (code "150") (name "/PK3") (class "Default")
      (node (ref "U14") (pin "D8") (pinfunction "PK3_D8") (pintype "passive"))
    )
    (net (code "151") (name "/STLK_MCO") (class "Default")
      (node (ref "SB19") (pin "1") (pinfunction "1_1") (pintype "passive"))
    )
    (net (code "152") (name "/SWO") (class "Default")
      (node (ref "SB7") (pin "1") (pinfunction "1_1") (pintype "passive"))
    )
    (net (code "153") (name "/USB_FS1_N") (class "Default")
      (node (ref "U14") (pin "C15") (pinfunction "PA11_C15") (pintype "passive"))
    )
    (net (code "154") (name "/USB_FS1_P") (class "Default")
      (node (ref "U14") (pin "B15") (pinfunction "PA12_B15") (pintype "passive"))
    )
    (net (code "155") (name "/uSD_D1") (class "Default")
      (node (ref "R135") (pin "2") (pinfunction "2_2") (pintype "passive"))
    )
    (net (code "156") (name "DSI_VDD12") (class "Default")
      (node (ref "C86") (pin "1") (pinfunction "1_1") (pintype "passive"))
      (node (ref "C87") (pin "2") (pinfunction "2_2") (pintype "passive"))
      (node (ref "SB14") (pin "1") (pinfunction "1_1") (pintype "passive"))
      (node (ref "U14") (pin "G13") (pinfunction "DSI_VDD12_G13") (pintype "passive"))
    )
    (net (code "157") (name "GND") (class "Default")
      (node (ref "C53") (pin "2") (pinfunction "2_2") (pintype "passive"))
      (node (ref "C54") (pin "2") (pinfunction "2_2") (pintype "passive"))
      (node (ref "C60") (pin "2") (pinfunction "2_2") (pintype "passive"))
      (node (ref "C65") (pin "2") (pinfunction "2_2") (pintype "passive"))
      (node (ref "C67") (pin "2") (pinfunction "2_2") (pintype "passive"))
      (node (ref "C68") (pin "2") (pinfunction "2_2") (pintype "passive"))
      (node (ref "C69") (pin "2") (pinfunction "2_2") (pintype "passive"))
      (node (ref "C70") (pin "2") (pinfunction "2_2") (pintype "passive"))
      (node (ref "C71") (pin "2") (pinfunction "2_2") (pintype "passive"))
      (node (ref "C72") (pin "2") (pinfunction "2_2") (pintype "passive"))
      (node (ref "C73") (pin "2") (pinfunction "2_2") (pintype "passive"))
      (node (ref "C74") (pin "2") (pinfunction "2_2") (pintype "passive"))
      (node (ref "C75") (pin "2") (pinfunction "2_2") (pintype "passive"))
      (node (ref "C76") (pin "2") (pinfunction "2_2") (pintype "passive"))
      (node (ref "C77") (pin "1") (pinfunction "1_1") (pintype "passive"))
      (node (ref "C78") (pin "1") (pinfunction "1_1") (pintype "passive"))
      (node (ref "C80") (pin "2") (pinfunction "2_2") (pintype "passive"))
      (node (ref "C81") (pin "2") (pinfunction "2_2") (pintype "passive"))
      (node (ref "C83") (pin "2") (pinfunction "2_2") (pintype "passive"))
      (node (ref "C84") (pin "2") (pinfunction "2_2") (pintype "passive"))
      (node (ref "C85") (pin "2") (pinfunction "2_2") (pintype "passive"))
      (node (ref "C86") (pin "2") (pinfunction "2_2") (pintype "passive"))
      (node (ref "C87") (pin "1") (pinfunction "1_1") (pintype "passive"))
      (node (ref "C88") (pin "2") (pinfunction "2_2") (pintype "passive"))
      (node (ref "C89") (pin "2") (pinfunction "2_2") (pintype "passive"))
      (node (ref "C90") (pin "2") (pinfunction "2_2") (pintype "passive"))
      (node (ref "C91") (pin "2") (pinfunction "2_2") (pintype "passive"))
      (node (ref "C92") (pin "2") (pinfunction "2_2") (pintype "passive"))
      (node (ref "C93") (pin "2") (pinfunction "2_2") (pintype "passive"))
      (node (ref "C94") (pin "2") (pinfunction "2_2") (pintype "passive"))
      (node (ref "C95") (pin "2") (pinfunction "2_2") (pintype "passive"))
      (node (ref "C96") (pin "2") (pinfunction "2_2") (pintype "passive"))
      (node (ref "C98") (pin "2") (pinfunction "2_2") (pintype "passive"))
      (node (ref "R122") (pin "1") (pinfunction "1_1") (pintype "passive"))
      (node (ref "R144") (pin "2") (pinfunction "2_2") (pintype "passive"))
      (node (ref "SB15") (pin "1") (pinfunction "1_1") (pintype "passive"))
      (node (ref "U14") (pin "F10") (pinfunction "VSS2_F10") (pintype "passive"))
      (node (ref "U14") (pin "F2") (pinfunction "VSS13_VSS18_F2") (pintype "passive"))
      (node (ref "U14") (pin "F6") (pinfunction "VSS3_F6") (pintype "passive"))
      (node (ref "U14") (pin "F7") (pinfunction "VSS11_F7") (pintype "passive"))
      (node (ref "U14") (pin "F8") (pinfunction "VSS10_F8") (pintype "passive"))
      (node (ref "U14") (pin "F9") (pinfunction "VSS15_F9") (pintype "passive"))
      (node (ref "U14") (pin "G10") (pinfunction "VSS9_G10") (pintype "passive"))
      (node (ref "U14") (pin "G12") (pinfunction "DSI_VSS_G12") (pintype "passive"))
      (node (ref "U14") (pin "G6") (pinfunction "VSS17_G6") (pintype "passive"))
      (node (ref "U14") (pin "H10") (pinfunction "VSS20_H10") (pintype "passive"))
      (node (ref "U14") (pin "H6") (pinfunction "VSS5_H6") (pintype "passive"))
      (node (ref "U14") (pin "J10") (pinfunction "VSS8_J10") (pintype "passive"))
      (node (ref "U14") (pin "J6") (pinfunction "VSS12_J6") (pintype "passive"))
      (node (ref "U14") (pin "K10") (pinfunction "VSS14_K10") (pintype "passive"))
      (node (ref "U14") (pin "K6") (pinfunction "VSS4_K6") (pintype "passive"))
      (node (ref "U14") (pin "K7") (pinfunction "VSS6_K7") (pintype "passive"))
      (node (ref "U14") (pin "K8") (pinfunction "VSS7_K8") (pintype "passive"))
      (node (ref "U14") (pin "K9") (pinfunction "VSS1_K9") (pintype "passive"))
      (node (ref "U14") (pin "L6") (pinfunction "VSS19_L6") (pintype "passive"))
      (node (ref "U14") (pin "M1") (pinfunction "VSSA_M1") (pintype "passive"))
      (node (ref "U14") (pin "N1") (pinfunction "VREF-_N1") (pintype "passive"))
    )
    (net (code "158") (name "Net-(C93-Pad1)") (class "Default")
      (node (ref "C93") (pin "1") (pinfunction "1_1") (pintype "passive"))
      (node (ref "R132") (pin "1") (pinfunction "1_1") (pintype "passive"))
      (node (ref "X3") (pin "1") (pinfunction "1_1") (pintype "passive"))
    )
    (net (code "159") (name "Net-(C94-Pad1)") (class "Default")
      (node (ref "C94") (pin "1") (pinfunction "1_1") (pintype "passive"))
      (node (ref "R133") (pin "1") (pinfunction "1_1") (pintype "passive"))
      (node (ref "X3") (pin "2") (pinfunction "2_2") (pintype "passive"))
    )
    (net (code "160") (name "Net-(R143-Pad2)") (class "Default")
      (node (ref "R143") (pin "2") (pinfunction "2_2") (pintype "passive"))
      (node (ref "SB15") (pin "2") (pinfunction "2_2") (pintype "passive"))
    )
    (net (code "161") (name "Net-(U14A-PDR_ON)") (class "Default")
      (node (ref "R144") (pin "1") (pinfunction "1_1") (pintype "passive"))
      (node (ref "R149") (pin "1") (pinfunction "1_1") (pintype "passive"))
      (node (ref "U14") (pin "E5") (pinfunction "PDR_ON_E5") (pintype "passive"))
    )
    (net (code "162") (name "Net-(U14C-BYPASS-REG)") (class "Default")
      (node (ref "R122") (pin "2") (pinfunction "2_2") (pintype "passive"))
      (node (ref "U14") (pin "L5") (pinfunction "BYPASS-REG_L5") (pintype "passive"))
    )
    (net (code "163") (name "Net-(U14C-DSI_VCAP)") (class "Default")
      (node (ref "C81") (pin "1") (pinfunction "1_1") (pintype "passive"))
      (node (ref "SB14") (pin "2") (pinfunction "2_2") (pintype "passive"))
      (node (ref "U14") (pin "K12") (pinfunction "DSI_VCAP_K12") (pintype "passive"))
    )
    (net (code "164") (name "Net-(U14C-VCAP1)") (class "Default")
      (node (ref "C76") (pin "1") (pinfunction "1_1") (pintype "passive"))
      (node (ref "U14") (pin "L11") (pinfunction "VCAP1_L11") (pintype "passive"))
    )
    (net (code "165") (name "Net-(U14C-VCAP2)") (class "Default")
      (node (ref "C96") (pin "1") (pinfunction "1_1") (pintype "passive"))
      (node (ref "U14") (pin "E11") (pinfunction "VCAP2_E11") (pintype "passive"))
    )
    (net (code "166") (name "Net-(X2-OSC2)") (class "Default")
      (node (ref "C85") (pin "1") (pinfunction "1_1") (pintype "passive"))
      (node (ref "R131") (pin "2") (pinfunction "2_2") (pintype "passive"))
      (node (ref "X2") (pin "2") (pinfunction "OSC2_2") (pintype "passive"))
    )
    (net (code "167") (name "VBUS_FS1") (class "Default")
      (node (ref "U14") (pin "E15") (pinfunction "PA9_E15") (pintype "passive"))
    )
    (net (code "168") (name "VDDA") (class "Default")
      (node (ref "C65") (pin "1") (pinfunction "1_1") (pintype "passive"))
      (node (ref "C77") (pin "2") (pinfunction "2_2") (pintype "passive"))
      (node (ref "L5") (pin "2") (pinfunction "2_2") (pintype "passive"))
      (node (ref "R123") (pin "1") (pinfunction "1_1") (pintype "passive"))
      (node (ref "U14") (pin "R1") (pinfunction "VDDA_R1") (pintype "passive"))
    )
    (net (code "169") (name "VDD_MCU") (class "Default")
      (node (ref "C53") (pin "1") (pinfunction "1_1") (pintype "passive"))
      (node (ref "C54") (pin "1") (pinfunction "1_1") (pintype "passive"))
      (node (ref "C60") (pin "1") (pinfunction "1_1") (pintype "passive"))
      (node (ref "C67") (pin "1") (pinfunction "1_1") (pintype "passive"))
      (node (ref "C68") (pin "1") (pinfunction "1_1") (pintype "passive"))
      (node (ref "C69") (pin "1") (pinfunction "1_1") (pintype "passive"))
      (node (ref "C70") (pin "1") (pinfunction "1_1") (pintype "passive"))
      (node (ref "C71") (pin "1") (pinfunction "1_1") (pintype "passive"))
      (node (ref "C72") (pin "1") (pinfunction "1_1") (pintype "passive"))
      (node (ref "C73") (pin "1") (pinfunction "1_1") (pintype "passive"))
      (node (ref "C74") (pin "1") (pinfunction "1_1") (pintype "passive"))
      (node (ref "C75") (pin "1") (pinfunction "1_1") (pintype "passive"))
      (node (ref "C84") (pin "1") (pinfunction "1_1") (pintype "passive"))
      (node (ref "C88") (pin "1") (pinfunction "1_1") (pintype "passive"))
      (node (ref "C89") (pin "1") (pinfunction "1_1") (pintype "passive"))
      (node (ref "C90") (pin "1") (pinfunction "1_1") (pintype "passive"))
      (node (ref "C91") (pin "1") (pinfunction "1_1") (pintype "passive"))
      (node (ref "C92") (pin "1") (pinfunction "1_1") (pintype "passive"))
      (node (ref "C95") (pin "1") (pinfunction "1_1") (pintype "passive"))
      (node (ref "C98") (pin "1") (pinfunction "1_1") (pintype "passive"))
      (node (ref "L5") (pin "1") (pinfunction "1_1") (pintype "passive"))
      (node (ref "U14") (pin "E10") (pinfunction "VDD15_E10") (pintype "passive"))
      (node (ref "U14") (pin "E7") (pinfunction "VDD3_E7") (pintype "passive"))
      (node (ref "U14") (pin "E8") (pinfunction "VDD11_E8") (pintype "passive"))
      (node (ref "U14") (pin "E9") (pinfunction "VDD10_E9") (pintype "passive"))
      (node (ref "U14") (pin "F11") (pinfunction "VDD2_F11") (pintype "passive"))
      (node (ref "U14") (pin "F4") (pinfunction "VDD13_F4") (pintype "passive"))
      (node (ref "U14") (pin "F5") (pinfunction "VDD17_F5") (pintype "passive"))
      (node (ref "U14") (pin "G11") (pinfunction "VDD_USB33_G11") (pintype "passive"))
      (node (ref "U14") (pin "G5") (pinfunction "VDD18_G5") (pintype "passive"))
      (node (ref "U14") (pin "H11") (pinfunction "VDD_VREGDSI_H11") (pintype "passive"))
      (node (ref "U14") (pin "H5") (pinfunction "VDD5_H5") (pintype "passive"))
      (node (ref "U14") (pin "J11") (pinfunction "VDD8_J11") (pintype "passive"))
      (node (ref "U14") (pin "J5") (pinfunction "VDD12_J5") (pintype "passive"))
      (node (ref "U14") (pin "K11") (pinfunction "VDD14_K11") (pintype "passive"))
      (node (ref "U14") (pin "K5") (pinfunction "VDD4_K5") (pintype "passive"))
      (node (ref "U14") (pin "L10") (pinfunction "VDD1_L10") (pintype "passive"))
      (node (ref "U14") (pin "L7") (pinfunction "VDD19_L7") (pintype "passive"))
      (node (ref "U14") (pin "L8") (pinfunction "VDD6_L8") (pintype "passive"))
      (node (ref "U14") (pin "L9") (pinfunction "VDD7_L9") (pintype "passive"))
    )
    (net (code "170") (name "VREF+") (class "Default")
      (node (ref "C78") (pin "2") (pinfunction "2_2") (pintype "passive"))
      (node (ref "C80") (pin "1") (pinfunction "1_1") (pintype "passive"))
      (node (ref "R123") (pin "2") (pinfunction "2_2") (pintype "passive"))
      (node (ref "U14") (pin "P1") (pinfunction "VREF+_P1") (pintype "passive"))
    )
    (net (code "171") (name "unconnected-(U14A-PJ0-PadR6)") (class "Default")
      (node (ref "U14") (pin "R6") (pinfunction "PJ0_R6") (pintype "passive+no_connect"))
    )
    (net (code "172") (name "unconnected-(U14A-PJ1-PadR7)") (class "Default")
      (node (ref "U14") (pin "R7") (pinfunction "PJ1_R7") (pintype "passive+no_connect"))
    )
    (net (code "173") (name "unconnected-(U14A-PJ3-PadN8)") (class "Default")
      (node (ref "U14") (pin "N8") (pinfunction "PJ3_N8") (pintype "passive+no_connect"))
    )
    (net (code "174") (name "unconnected-(U14A-PJ4-PadM9)") (class "Default")
      (node (ref "U14") (pin "M9") (pinfunction "PJ4_M9") (pintype "passive+no_connect"))
    )
    (net (code "175") (name "unconnected-(U14A-PJ12-PadB10)") (class "Default")
      (node (ref "U14") (pin "B10") (pinfunction "PJ12_B10") (pintype "passive+no_connect"))
    )
    (net (code "176") (name "unconnected-(U14A-PJ13-PadB9)") (class "Default")
      (node (ref "U14") (pin "B9") (pinfunction "PJ13_B9") (pintype "passive+no_connect"))
    )
    (net (code "177") (name "unconnected-(U14A-PJ14-PadC9)") (class "Default")
      (node (ref "U14") (pin "C9") (pinfunction "PJ14_C9") (pintype "passive+no_connect"))
    )
    (net (code "178") (name "unconnected-(U14A-PJ15-PadD10)") (class "Default")
      (node (ref "U14") (pin "D10") (pinfunction "PJ15_D10") (pintype "passive+no_connect"))
    )
    (net (code "179") (name "unconnected-(U14A-PK4-PadD7)") (class "Default")
      (node (ref "U14") (pin "D7") (pinfunction "PK4_D7") (pintype "passive+no_connect"))
    )
    (net (code "180") (name "unconnected-(U14A-PK5-PadC6)") (class "Default")
      (node (ref "U14") (pin "C6") (pinfunction "PK5_C6") (pintype "passive+no_connect"))
    )
    (net (code "181") (name "unconnected-(U14A-PK6-PadC5)") (class "Default")
      (node (ref "U14") (pin "C5") (pinfunction "PK6_C5") (pintype "passive+no_connect"))
    )
    (net (code "182") (name "unconnected-(U14A-PK7-PadC4)") (class "Default")
      (node (ref "U14") (pin "C4") (pinfunction "PK7_C4") (pintype "passive+no_connect"))
    )
    (net (code "183") (name "unconnected-(U14B-PD11-PadN10)") (class "Default")
      (node (ref "U14") (pin "N10") (pinfunction "PD11_N10") (pintype "passive+no_connect"))
    )
    (net (code "184") (name "unconnected-(U14B-PI8-ANTI_TAMP2-PadC2)") (class "Default")
      (node (ref "U14") (pin "C2") (pinfunction "PI8-ANTI_TAMP2_C2") (pintype "passive+no_connect"))
    )
    (net (code "185") (name "unconnected-(U14B-PI11-PadF3)") (class "Default")
      (node (ref "U14") (pin "F3") (pinfunction "PI11_F3") (pintype "passive+no_connect"))
    )
    (net (code "186") (name "unconnected-(U14B-PI12-PadE3)") (class "Default")
      (node (ref "U14") (pin "E3") (pinfunction "PI12_E3") (pintype "passive+no_connect"))
    )
    (net (code "187") (name "unconnected-(U14B-PI13-PadG3)") (class "Default")
      (node (ref "U14") (pin "G3") (pinfunction "PI13_G3") (pintype "passive+no_connect"))
    )
    (net (code "188") (name "unconnected-(U14B-PI14-PadH3)") (class "Default")
      (node (ref "U14") (pin "H3") (pinfunction "PI14_H3") (pintype "passive+no_connect"))
    )
    (net (code "189") (name "unconnected-(U14B-PI15-PadG4)") (class "Default")
      (node (ref "U14") (pin "G4") (pinfunction "PI15_G4") (pintype "passive+no_connect"))
    )
  )
)
